# Myscheme.net
KiCad netlist of a schematic drawn in Altium Designer
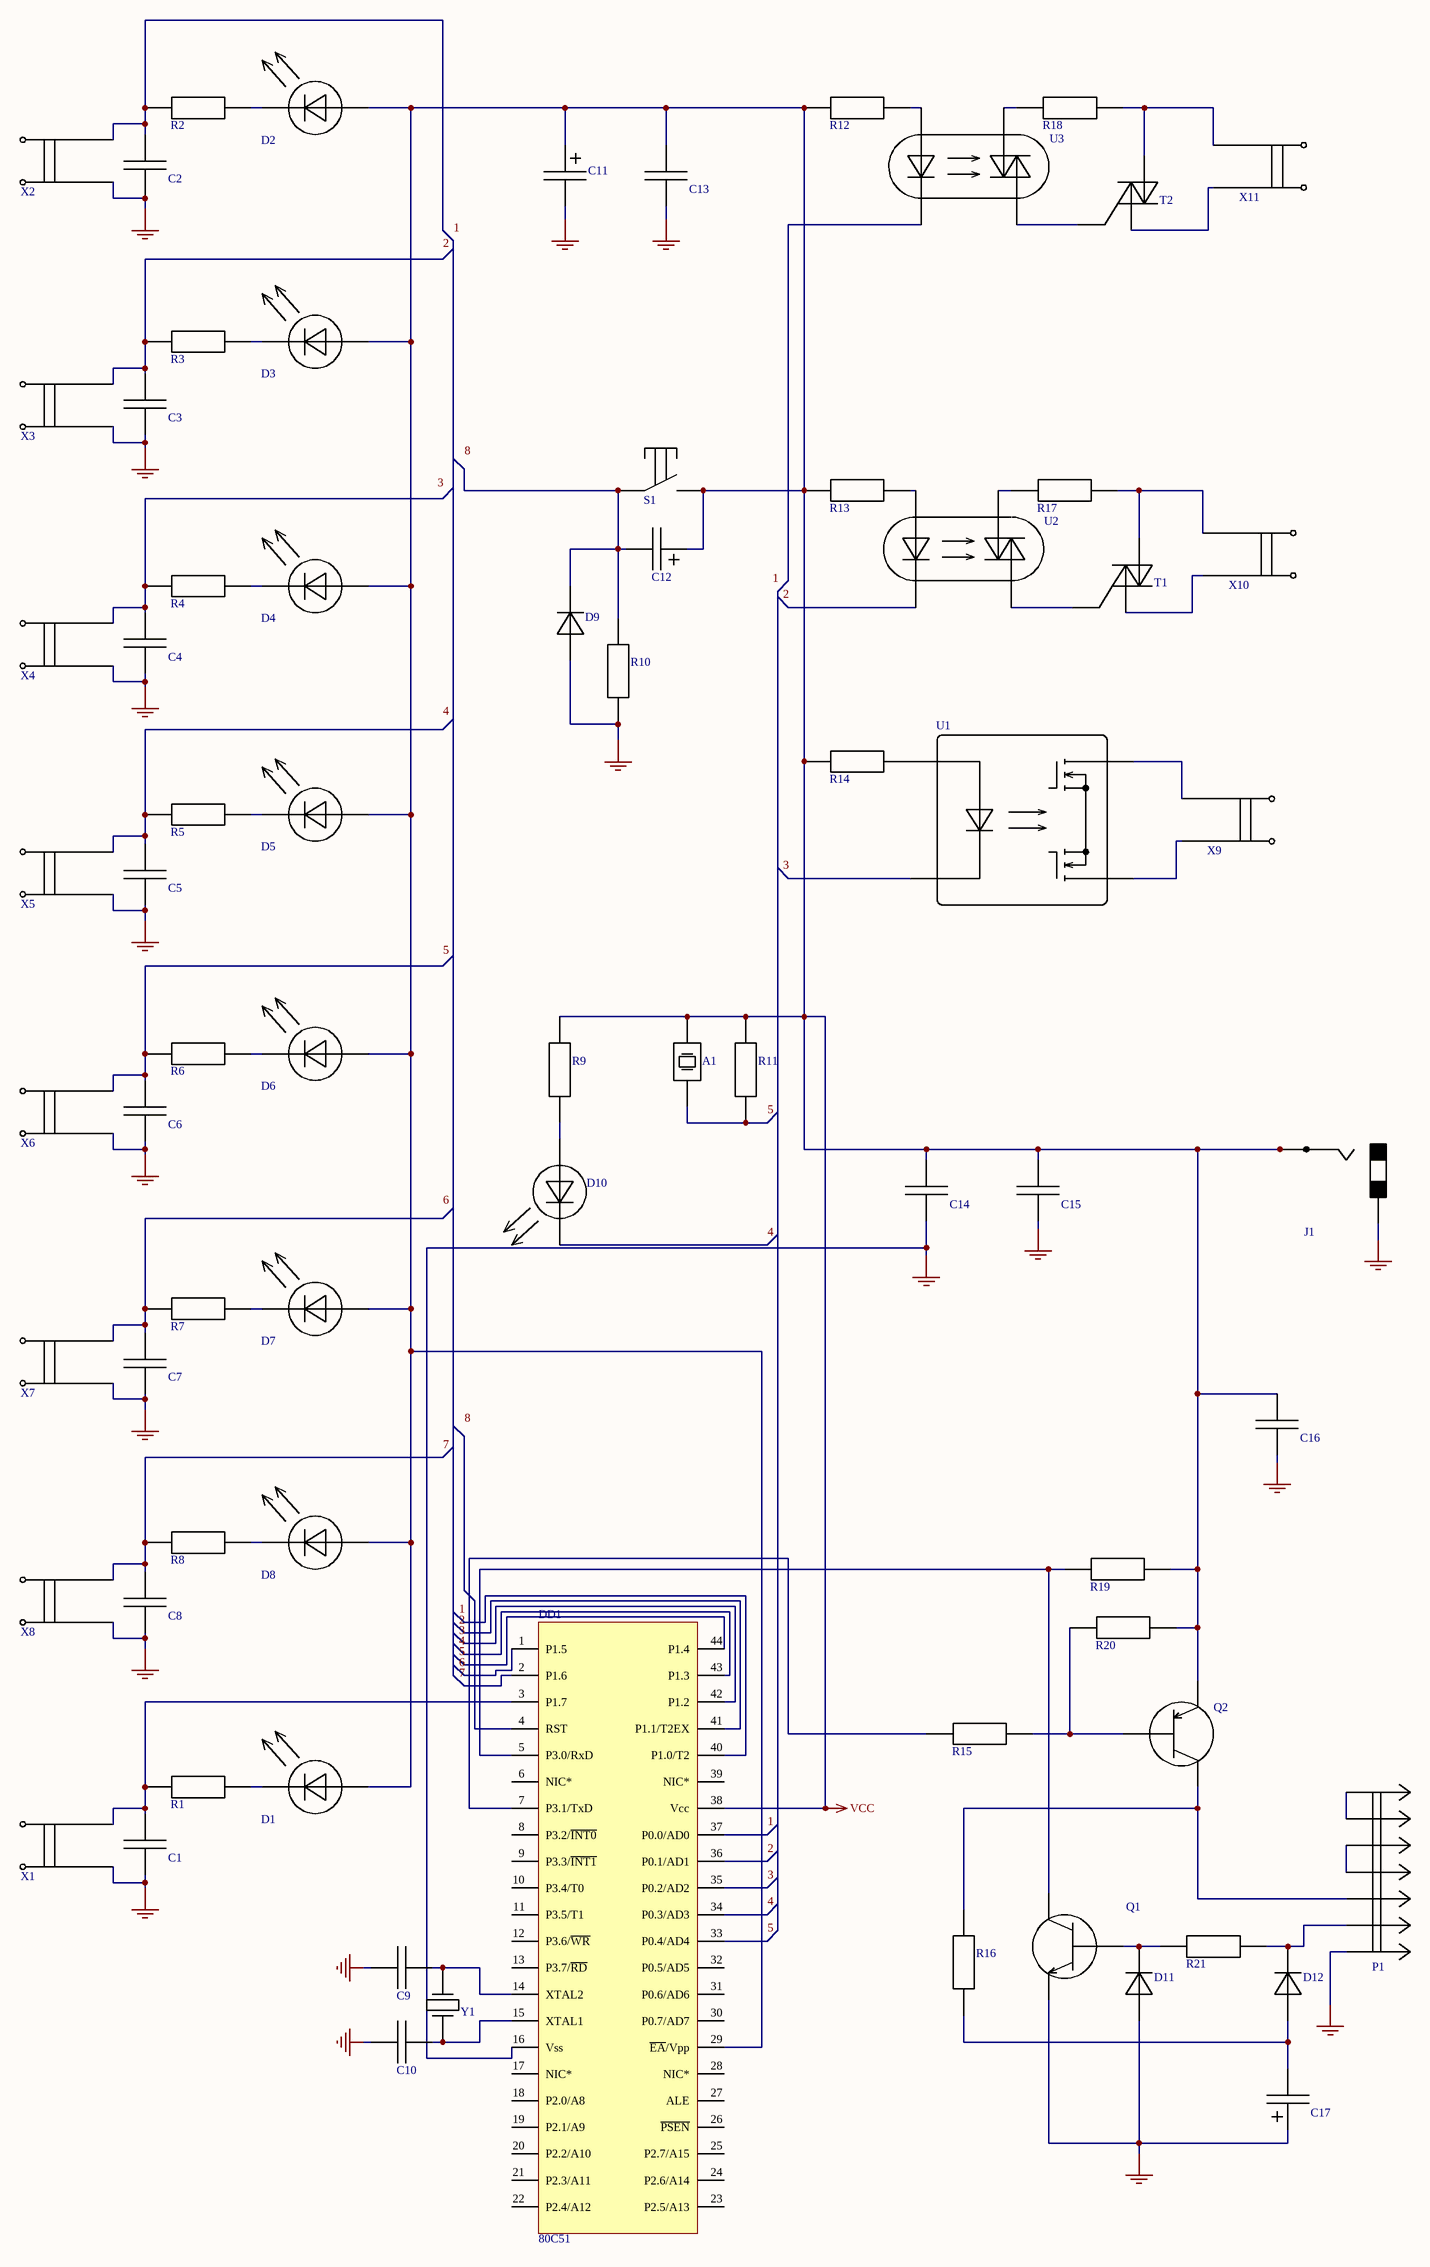
[diagram p0: Myscheme.SchDoc]

(export (version "E")
  (design (tool "Eeschema 10.0.6"))
  (components
    (comp (ref "A1")
      (value "acoustic")
      (footprint "PcbLib1:BUZZER_RM_5MM_PKM13EPYH4002-B0(Primary) - duplicate")
      (libsource (lib "Shestakov") (part "acoustic"))
    )
    (comp (ref "C1")
      (value "Cap")
      (footprint "RAD-0.3")
      (description "Capacitor")
      (libsource (lib "Shestakov") (part "Cap"))
    )
    (comp (ref "C2")
      (value "Cap")
      (footprint "RAD-0.3")
      (description "Capacitor")
      (libsource (lib "Shestakov") (part "Cap"))
    )
    (comp (ref "C3")
      (value "Cap")
      (footprint "RAD-0.3")
      (description "Capacitor")
      (libsource (lib "Shestakov") (part "Cap"))
    )
    (comp (ref "C4")
      (value "Cap")
      (footprint "RAD-0.3")
      (description "Capacitor")
      (libsource (lib "Shestakov") (part "Cap"))
    )
    (comp (ref "C5")
      (value "Cap")
      (footprint "RAD-0.3")
      (description "Capacitor")
      (libsource (lib "Shestakov") (part "Cap"))
    )
    (comp (ref "C6")
      (value "Cap")
      (footprint "RAD-0.3")
      (description "Capacitor")
      (libsource (lib "Shestakov") (part "Cap"))
    )
    (comp (ref "C7")
      (value "Cap")
      (footprint "RAD-0.3")
      (description "Capacitor")
      (libsource (lib "Shestakov") (part "Cap"))
    )
    (comp (ref "C8")
      (value "Cap")
      (footprint "RAD-0.3")
      (description "Capacitor")
      (libsource (lib "Shestakov") (part "Cap"))
    )
    (comp (ref "C9")
      (value "Cap")
      (footprint "RAD-0.3")
      (description "Capacitor")
      (libsource (lib "Shestakov") (part "Cap"))
    )
    (comp (ref "C10")
      (value "Cap")
      (footprint "RAD-0.3")
      (description "Capacitor")
      (libsource (lib "Shestakov") (part "Cap"))
    )
    (comp (ref "C11") (value "Cap+") (footprint "RB7.6-15") (libsource (lib "Shestakov") (part "Cap+")))
    (comp (ref "C12") (value "Cap+") (footprint "RB7.6-15") (libsource (lib "Shestakov") (part "Cap+")))
    (comp (ref "C13")
      (value "Cap")
      (footprint "RAD-0.3")
      (description "Capacitor")
      (libsource (lib "Shestakov") (part "Cap"))
    )
    (comp (ref "C14")
      (value "Cap")
      (footprint "RAD-0.3")
      (description "Capacitor")
      (libsource (lib "Shestakov") (part "Cap"))
    )
    (comp (ref "C15")
      (value "Cap")
      (footprint "RAD-0.3")
      (description "Capacitor")
      (libsource (lib "Shestakov") (part "Cap"))
    )
    (comp (ref "C16")
      (value "Cap")
      (footprint "RAD-0.3")
      (description "Capacitor")
      (libsource (lib "Shestakov") (part "Cap"))
    )
    (comp (ref "C17") (value "Cap+") (footprint "RB7.6-15") (libsource (lib "Shestakov") (part "Cap+")))
    (comp (ref "D1") (value "LED") (footprint "LED-1") (libsource (lib "Integrated_Library2") (part "LED")))
    (comp (ref "D2") (value "LED") (footprint "LED-1") (libsource (lib "Integrated_Library2") (part "LED")))
    (comp (ref "D3") (value "LED") (footprint "LED-1") (libsource (lib "Integrated_Library2") (part "LED")))
    (comp (ref "D4") (value "LED") (footprint "LED-1") (libsource (lib "Integrated_Library2") (part "LED")))
    (comp (ref "D5") (value "LED") (footprint "LED-1") (libsource (lib "Integrated_Library2") (part "LED")))
    (comp (ref "D6") (value "LED") (footprint "LED-1") (libsource (lib "Integrated_Library2") (part "LED")))
    (comp (ref "D7") (value "LED") (footprint "LED-1") (libsource (lib "Integrated_Library2") (part "LED")))
    (comp (ref "D8") (value "LED") (footprint "LED-1") (libsource (lib "Integrated_Library2") (part "LED")))
    (comp (ref "D9")
      (value "~")
      (footprint "PcbLib1:DIOAD730W55L340D162P_1N4148(Primary)")
      (description "1N4148")
      (libsource (lib "Shestakov") (part "1N4148"))
    )
    (comp (ref "D10") (value "LED") (footprint "LED-1") (libsource (lib "Integrated_Library2") (part "LED")))
    (comp (ref "D11")
      (value "~")
      (footprint "PcbLib1:DIOAD730W55L340D162P_1N4148(Primary)")
      (description "1N4148")
      (libsource (lib "Shestakov") (part "1N4148"))
    )
    (comp (ref "D12")
      (value "~")
      (footprint "PcbLib1:DIOAD730W55L340D162P_1N4148(Primary)")
      (description "1N4148")
      (libsource (lib "Shestakov") (part "1N4148"))
    )
    (comp (ref "DD1")
      (value "80C51")
      (footprint "QFP80P1260X1260X210-44N")
      (libsource (lib "Shestakov") (part "80C51"))
    )
    (comp (ref "J1")
      (value "phonejack")
      (footprint "PcbLib1:JACK/6-V2")
      (libsource (lib "Shestakov") (part "phonejack"))
    )
    (comp (ref "P1") (value "plug") (footprint "PIN1") (libsource (lib "Shestakov") (part "plug")))
    (comp (ref "Q1")
      (value "~")
      (footprint "PcbLib1:TO-92A")
      (description "КТ315Б")
      (libsource (lib "Shestakov") (part "КТ315Б"))
    )
    (comp (ref "Q2")
      (value "~")
      (footprint "PcbLib1:TO92127P520H534-3")
      (description "КТ361Б")
      (libsource (lib "Shestakov") (part "КТ361Б"))
    )
    (comp (ref "R1")
      (value "Res")
      (footprint "PCBComponent_1")
      (libsource (lib "Integrated_Library2") (part "Res"))
    )
    (comp (ref "R2")
      (value "Res")
      (footprint "PCBComponent_1")
      (libsource (lib "Integrated_Library2") (part "Res"))
    )
    (comp (ref "R3")
      (value "Res")
      (footprint "PCBComponent_1")
      (libsource (lib "Integrated_Library2") (part "Res"))
    )
    (comp (ref "R4")
      (value "Res")
      (footprint "PCBComponent_1")
      (libsource (lib "Integrated_Library2") (part "Res"))
    )
    (comp (ref "R5")
      (value "Res")
      (footprint "PCBComponent_1")
      (libsource (lib "Integrated_Library2") (part "Res"))
    )
    (comp (ref "R6")
      (value "Res")
      (footprint "PCBComponent_1")
      (libsource (lib "Integrated_Library2") (part "Res"))
    )
    (comp (ref "R7")
      (value "Res")
      (footprint "PCBComponent_1")
      (libsource (lib "Integrated_Library2") (part "Res"))
    )
    (comp (ref "R8")
      (value "Res")
      (footprint "PCBComponent_1")
      (libsource (lib "Integrated_Library2") (part "Res"))
    )
    (comp (ref "R9")
      (value "Res")
      (footprint "PCBComponent_1")
      (libsource (lib "Integrated_Library2") (part "Res"))
    )
    (comp (ref "R10")
      (value "Res")
      (footprint "PCBComponent_1")
      (libsource (lib "Integrated_Library2") (part "Res"))
    )
    (comp (ref "R11")
      (value "Res")
      (footprint "PCBComponent_1")
      (libsource (lib "Integrated_Library2") (part "Res"))
    )
    (comp (ref "R12")
      (value "Res")
      (footprint "PCBComponent_1")
      (libsource (lib "Integrated_Library2") (part "Res"))
    )
    (comp (ref "R13")
      (value "Res")
      (footprint "PCBComponent_1")
      (libsource (lib "Integrated_Library2") (part "Res"))
    )
    (comp (ref "R14")
      (value "Res")
      (footprint "PCBComponent_1")
      (libsource (lib "Integrated_Library2") (part "Res"))
    )
    (comp (ref "R15")
      (value "Res")
      (footprint "PCBComponent_1")
      (libsource (lib "Integrated_Library2") (part "Res"))
    )
    (comp (ref "R16")
      (value "Res")
      (footprint "PCBComponent_1")
      (libsource (lib "Integrated_Library2") (part "Res"))
    )
    (comp (ref "R17")
      (value "Res")
      (footprint "PCBComponent_1")
      (libsource (lib "Integrated_Library2") (part "Res"))
    )
    (comp (ref "R18")
      (value "Res")
      (footprint "PCBComponent_1")
      (libsource (lib "Integrated_Library2") (part "Res"))
    )
    (comp (ref "R19")
      (value "Res")
      (footprint "PCBComponent_1")
      (libsource (lib "Integrated_Library2") (part "Res"))
    )
    (comp (ref "R20")
      (value "Res")
      (footprint "PCBComponent_1")
      (libsource (lib "Integrated_Library2") (part "Res"))
    )
    (comp (ref "R21")
      (value "Res")
      (footprint "PCBComponent_1")
      (libsource (lib "Integrated_Library2") (part "Res"))
    )
    (comp (ref "S1") (value "SW-SPST") (footprint "SPST-2") (libsource (lib "Shestakov") (part "SW-SPST")))
    (comp (ref "T1")
      (value "~")
      (footprint "PcbLib1:TO-220-ALT")
      (description "BT138-600")
      (libsource (lib "Shestakov") (part "BT138-600"))
    )
    (comp (ref "T2")
      (value "~")
      (footprint "PcbLib1:TO-220-ALT")
      (description "BT138-600")
      (libsource (lib "Shestakov") (part "BT138-600"))
    )
    (comp (ref "U1")
      (value "~")
      (footprint "PcbLib1:SOIC254P610X218-4N")
      (description "CPC1035N")
      (libsource (lib "Shestakov") (part "CPC1035N"))
    )
    (comp (ref "U2")
      (value "~")
      (footprint "PcbLib1:SOIC254P1016X460-6N")
      (description "MOC3020M")
      (libsource (lib "Shestakov") (part "MOC3020M"))
    )
    (comp (ref "U3")
      (value "~")
      (footprint "PcbLib1:SOIC254P1016X460-6N")
      (description "MOC3020M")
      (libsource (lib "Shestakov") (part "MOC3020M"))
    )
    (comp (ref "X1")
      (value "Entrance")
      (footprint "PcbLib1:P-2059-301/998-403_2059-301/998-403(Primary)")
      (libsource (lib "Shestakov") (part "Entrance"))
    )
    (comp (ref "X2")
      (value "Entrance")
      (footprint "PcbLib1:P-2059-301/998-403_2059-301/998-403(Primary)")
      (libsource (lib "Shestakov") (part "Entrance"))
    )
    (comp (ref "X3")
      (value "Entrance")
      (footprint "PcbLib1:P-2059-301/998-403_2059-301/998-403(Primary)")
      (libsource (lib "Shestakov") (part "Entrance"))
    )
    (comp (ref "X4")
      (value "Entrance")
      (footprint "PcbLib1:P-2059-301/998-403_2059-301/998-403(Primary)")
      (libsource (lib "Shestakov") (part "Entrance"))
    )
    (comp (ref "X5")
      (value "Entrance")
      (footprint "PcbLib1:P-2059-301/998-403_2059-301/998-403(Primary)")
      (libsource (lib "Shestakov") (part "Entrance"))
    )
    (comp (ref "X6")
      (value "Entrance")
      (footprint "PcbLib1:P-2059-301/998-403_2059-301/998-403(Primary)")
      (libsource (lib "Shestakov") (part "Entrance"))
    )
    (comp (ref "X7")
      (value "Entrance")
      (footprint "PcbLib1:P-2059-301/998-403_2059-301/998-403(Primary)")
      (libsource (lib "Shestakov") (part "Entrance"))
    )
    (comp (ref "X8")
      (value "Entrance")
      (footprint "PcbLib1:P-2059-301/998-403_2059-301/998-403(Primary)")
      (libsource (lib "Shestakov") (part "Entrance"))
    )
    (comp (ref "X9")
      (value "Entrance")
      (footprint "PcbLib1:P-2059-301/998-403_2059-301/998-403(Primary)")
      (libsource (lib "Shestakov") (part "Entrance"))
    )
    (comp (ref "X10")
      (value "Entrance")
      (footprint "PcbLib1:P-2059-301/998-403_2059-301/998-403(Primary)")
      (libsource (lib "Shestakov") (part "Entrance"))
    )
    (comp (ref "X11")
      (value "Entrance")
      (footprint "PcbLib1:P-2059-301/998-403_2059-301/998-403(Primary)")
      (libsource (lib "Shestakov") (part "Entrance"))
    )
    (comp (ref "Y1") (value "XTAL") (footprint "R38") (libsource (lib "Shestakov") (part "XTAL")))
  )
  (nets
    (net (code "9") (name "GND") (class "Default")
      (node (ref "C1") (pin "2") (pinfunction "2_2") (pintype "passive"))
      (node (ref "C10") (pin "2") (pinfunction "2_2") (pintype "passive"))
      (node (ref "C11") (pin "2") (pinfunction "2_2") (pintype "passive"))
      (node (ref "C13") (pin "2") (pinfunction "2_2") (pintype "passive"))
      (node (ref "C14") (pin "2") (pinfunction "2_2") (pintype "passive"))
      (node (ref "C15") (pin "2") (pinfunction "2_2") (pintype "passive"))
      (node (ref "C16") (pin "2") (pinfunction "2_2") (pintype "passive"))
      (node (ref "C17") (pin "1") (pinfunction "1_1") (pintype "passive"))
      (node (ref "C2") (pin "2") (pinfunction "2_2") (pintype "passive"))
      (node (ref "C3") (pin "2") (pinfunction "2_2") (pintype "passive"))
      (node (ref "C4") (pin "2") (pinfunction "2_2") (pintype "passive"))
      (node (ref "C5") (pin "2") (pinfunction "2_2") (pintype "passive"))
      (node (ref "C6") (pin "2") (pinfunction "2_2") (pintype "passive"))
      (node (ref "C7") (pin "2") (pinfunction "2_2") (pintype "passive"))
      (node (ref "C8") (pin "2") (pinfunction "2_2") (pintype "passive"))
      (node (ref "C9") (pin "2") (pinfunction "2_2") (pintype "passive"))
      (node (ref "D11") (pin "C") (pinfunction "C_C") (pintype "passive"))
      (node (ref "D9") (pin "C") (pinfunction "C_C") (pintype "passive"))
      (node (ref "DD1") (pin "16") (pinfunction "Vss_16") (pintype "power_in"))
      (node (ref "J1") (pin "5") (pinfunction "5_5") (pintype "passive"))
      (node (ref "P1") (pin "5") (pinfunction "5_5") (pintype "passive"))
      (node (ref "Q1") (pin "1") (pinfunction "1_1") (pintype "passive"))
      (node (ref "R10") (pin "2") (pinfunction "2_2") (pintype "passive"))
      (node (ref "X1") (pin "L1.2") (pinfunction "2_L1.2") (pintype "passive"))
      (node (ref "X2") (pin "L1.2") (pinfunction "2_L1.2") (pintype "passive"))
      (node (ref "X3") (pin "L1.2") (pinfunction "2_L1.2") (pintype "passive"))
      (node (ref "X4") (pin "L1.2") (pinfunction "2_L1.2") (pintype "passive"))
      (node (ref "X5") (pin "L1.2") (pinfunction "2_L1.2") (pintype "passive"))
      (node (ref "X6") (pin "L1.2") (pinfunction "2_L1.2") (pintype "passive"))
      (node (ref "X7") (pin "L1.2") (pinfunction "2_L1.2") (pintype "passive"))
      (node (ref "X8") (pin "L1.2") (pinfunction "2_L1.2") (pintype "passive"))
    )
    (net (code "10") (name "Net-(A1-PadPOS)") (class "Default")
      (node (ref "A1") (pin "POS") (pinfunction "POS_POS") (pintype "passive"))
      (node (ref "R11") (pin "2") (pinfunction "2_2") (pintype "passive"))
    )
    (net (code "11") (name "Net-(C12-Pad2)") (class "Default")
      (node (ref "C12") (pin "2") (pinfunction "2_2") (pintype "passive"))
      (node (ref "D9") (pin "A") (pinfunction "A_A") (pintype "passive"))
      (node (ref "R10") (pin "1") (pinfunction "1_1") (pintype "passive"))
      (node (ref "S1") (pin "1") (pinfunction "1_1") (pintype "passive"))
    )
    (net (code "12") (name "Net-(C17-Pad2)") (class "Default")
      (node (ref "C17") (pin "2") (pinfunction "2_2") (pintype "passive"))
      (node (ref "D12") (pin "C") (pinfunction "C_C") (pintype "passive"))
      (node (ref "R16") (pin "1") (pinfunction "1_1") (pintype "passive"))
    )
    (net (code "13") (name "Net-(D1-Pad1)") (class "Default")
      (node (ref "D1") (pin "1") (pinfunction "1_1") (pintype "passive"))
      (node (ref "R1") (pin "1") (pinfunction "1_1") (pintype "passive"))
    )
    (net (code "14") (name "Net-(D2-Pad1)") (class "Default")
      (node (ref "D2") (pin "1") (pinfunction "1_1") (pintype "passive"))
      (node (ref "R2") (pin "1") (pinfunction "1_1") (pintype "passive"))
    )
    (net (code "15") (name "Net-(D3-Pad1)") (class "Default")
      (node (ref "D3") (pin "1") (pinfunction "1_1") (pintype "passive"))
      (node (ref "R3") (pin "1") (pinfunction "1_1") (pintype "passive"))
    )
    (net (code "16") (name "Net-(D4-Pad1)") (class "Default")
      (node (ref "D4") (pin "1") (pinfunction "1_1") (pintype "passive"))
      (node (ref "R4") (pin "1") (pinfunction "1_1") (pintype "passive"))
    )
    (net (code "17") (name "Net-(D5-Pad1)") (class "Default")
      (node (ref "D5") (pin "1") (pinfunction "1_1") (pintype "passive"))
      (node (ref "R5") (pin "1") (pinfunction "1_1") (pintype "passive"))
    )
    (net (code "18") (name "Net-(D6-Pad1)") (class "Default")
      (node (ref "D6") (pin "1") (pinfunction "1_1") (pintype "passive"))
      (node (ref "R6") (pin "1") (pinfunction "1_1") (pintype "passive"))
    )
    (net (code "19") (name "Net-(D7-Pad1)") (class "Default")
      (node (ref "D7") (pin "1") (pinfunction "1_1") (pintype "passive"))
      (node (ref "R7") (pin "1") (pinfunction "1_1") (pintype "passive"))
    )
    (net (code "20") (name "Net-(D8-Pad1)") (class "Default")
      (node (ref "D8") (pin "1") (pinfunction "1_1") (pintype "passive"))
      (node (ref "R8") (pin "1") (pinfunction "1_1") (pintype "passive"))
    )
    (net (code "21") (name "Net-(D10-Pad2)") (class "Default")
      (node (ref "D10") (pin "2") (pinfunction "2_2") (pintype "passive"))
      (node (ref "R9") (pin "2") (pinfunction "2_2") (pintype "passive"))
    )
    (net (code "22") (name "Net-(D11-PadA)") (class "Default")
      (node (ref "D11") (pin "A") (pinfunction "A_A") (pintype "passive"))
      (node (ref "Q1") (pin "2") (pinfunction "2_2") (pintype "passive"))
      (node (ref "R21") (pin "1") (pinfunction "1_1") (pintype "passive"))
    )
    (net (code "23") (name "Net-(D12-PadA)") (class "Default")
      (node (ref "D12") (pin "A") (pinfunction "A_A") (pintype "passive"))
      (node (ref "P1") (pin "2") (pinfunction "2_2") (pintype "passive"))
      (node (ref "R21") (pin "2") (pinfunction "2_2") (pintype "passive"))
    )
    (net (code "24") (name "Net-(DD1-P1.7)") (class "Default")
      (node (ref "C1") (pin "1") (pinfunction "1_1") (pintype "passive"))
      (node (ref "DD1") (pin "3") (pinfunction "P1.7_3") (pintype "passive"))
      (node (ref "R1") (pin "2") (pinfunction "2_2") (pintype "passive"))
      (node (ref "X1") (pin "L1.1") (pinfunction "1_L1.1") (pintype "passive"))
    )
    (net (code "25") (name "Net-(DD1-P3.0{slash}RxD)") (class "Default")
      (node (ref "DD1") (pin "5") (pinfunction "P3.0/RxD_5") (pintype "passive"))
      (node (ref "Q1") (pin "3") (pinfunction "3_3") (pintype "passive"))
      (node (ref "R19") (pin "1") (pinfunction "1_1") (pintype "passive"))
    )
    (net (code "26") (name "Net-(DD1-P3.1{slash}TxD)") (class "Default")
      (node (ref "DD1") (pin "7") (pinfunction "P3.1/TxD_7") (pintype "passive"))
      (node (ref "R15") (pin "1") (pinfunction "1_1") (pintype "passive"))
    )
    (net (code "27") (name "Net-(DD1-XTAL1)") (class "Default")
      (node (ref "C10") (pin "1") (pinfunction "1_1") (pintype "passive"))
      (node (ref "DD1") (pin "15") (pinfunction "XTAL1_15") (pintype "passive"))
      (node (ref "Y1") (pin "1") (pinfunction "1_1") (pintype "passive"))
    )
    (net (code "28") (name "Net-(DD1-XTAL2)") (class "Default")
      (node (ref "C9") (pin "1") (pinfunction "1_1") (pintype "passive"))
      (node (ref "DD1") (pin "14") (pinfunction "XTAL2_14") (pintype "passive"))
      (node (ref "Y1") (pin "2") (pinfunction "2_2") (pintype "passive"))
    )
    (net (code "29") (name "Net-(P1-Pad3)") (class "Default")
      (node (ref "P1") (pin "3") (pinfunction "3_3") (pintype "passive"))
      (node (ref "Q2") (pin "3") (pinfunction "3_3") (pintype "passive"))
      (node (ref "R16") (pin "2") (pinfunction "2_2") (pintype "passive"))
    )
    (net (code "30") (name "Net-(P1-Pad4)") (class "Default")
      (node (ref "P1") (pin "4") (pinfunction "4_4") (pintype "passive"))
      (node (ref "P1") (pin "6") (pinfunction "6_6") (pintype "passive"))
    )
    (net (code "31") (name "Net-(P1-Pad7)") (class "Default")
      (node (ref "P1") (pin "7") (pinfunction "7_7") (pintype "passive"))
      (node (ref "P1") (pin "8") (pinfunction "8_8") (pintype "passive"))
    )
    (net (code "32") (name "Net-(Q2-Pad2)") (class "Default")
      (node (ref "Q2") (pin "2") (pinfunction "2_2") (pintype "passive"))
      (node (ref "R15") (pin "2") (pinfunction "2_2") (pintype "passive"))
      (node (ref "R20") (pin "1") (pinfunction "1_1") (pintype "passive"))
    )
    (net (code "33") (name "Net-(R12-Pad1)") (class "Default")
      (node (ref "R12") (pin "1") (pinfunction "1_1") (pintype "passive"))
      (node (ref "U3") (pin "1") (pinfunction "1_1") (pintype "passive"))
    )
    (net (code "34") (name "Net-(R13-Pad1)") (class "Default")
      (node (ref "R13") (pin "1") (pinfunction "1_1") (pintype "passive"))
      (node (ref "U2") (pin "1") (pinfunction "1_1") (pintype "passive"))
    )
    (net (code "35") (name "Net-(R14-Pad1)") (class "Default")
      (node (ref "R14") (pin "1") (pinfunction "1_1") (pintype "passive"))
      (node (ref "U1") (pin "1") (pinfunction "1_1") (pintype "passive"))
    )
    (net (code "36") (name "Net-(R17-Pad2)") (class "Default")
      (node (ref "R17") (pin "2") (pinfunction "2_2") (pintype "passive"))
      (node (ref "U2") (pin "6") (pinfunction "6_6") (pintype "passive"))
    )
    (net (code "37") (name "Net-(R18-Pad2)") (class "Default")
      (node (ref "R18") (pin "2") (pinfunction "2_2") (pintype "passive"))
      (node (ref "U3") (pin "6") (pinfunction "6_6") (pintype "passive"))
    )
    (net (code "38") (name "Net-(T1-PadOUT)") (class "Default")
      (node (ref "T1") (pin "OUT") (pinfunction "OUT_OUT") (pintype "passive"))
      (node (ref "U2") (pin "4") (pinfunction "4_4") (pintype "passive"))
    )
    (net (code "39") (name "Net-(T2-PadOUT)") (class "Default")
      (node (ref "T2") (pin "OUT") (pinfunction "OUT_OUT") (pintype "passive"))
      (node (ref "U3") (pin "4") (pinfunction "4_4") (pintype "passive"))
    )
    (net (code "40") (name "Net-(X2-1)") (class "Default")
      (node (ref "C2") (pin "1") (pinfunction "1_1") (pintype "passive"))
      (node (ref "R2") (pin "2") (pinfunction "2_2") (pintype "passive"))
      (node (ref "X2") (pin "L1.1") (pinfunction "1_L1.1") (pintype "passive"))
    )
    (net (code "41") (name "Net-(X3-1)") (class "Default")
      (node (ref "C3") (pin "1") (pinfunction "1_1") (pintype "passive"))
      (node (ref "R3") (pin "2") (pinfunction "2_2") (pintype "passive"))
      (node (ref "X3") (pin "L1.1") (pinfunction "1_L1.1") (pintype "passive"))
    )
    (net (code "42") (name "Net-(X4-1)") (class "Default")
      (node (ref "C4") (pin "1") (pinfunction "1_1") (pintype "passive"))
      (node (ref "R4") (pin "2") (pinfunction "2_2") (pintype "passive"))
      (node (ref "X4") (pin "L1.1") (pinfunction "1_L1.1") (pintype "passive"))
    )
    (net (code "43") (name "Net-(X5-1)") (class "Default")
      (node (ref "C5") (pin "1") (pinfunction "1_1") (pintype "passive"))
      (node (ref "R5") (pin "2") (pinfunction "2_2") (pintype "passive"))
      (node (ref "X5") (pin "L1.1") (pinfunction "1_L1.1") (pintype "passive"))
    )
    (net (code "44") (name "Net-(X6-1)") (class "Default")
      (node (ref "C6") (pin "1") (pinfunction "1_1") (pintype "passive"))
      (node (ref "R6") (pin "2") (pinfunction "2_2") (pintype "passive"))
      (node (ref "X6") (pin "L1.1") (pinfunction "1_L1.1") (pintype "passive"))
    )
    (net (code "45") (name "Net-(X7-1)") (class "Default")
      (node (ref "C7") (pin "1") (pinfunction "1_1") (pintype "passive"))
      (node (ref "R7") (pin "2") (pinfunction "2_2") (pintype "passive"))
      (node (ref "X7") (pin "L1.1") (pinfunction "1_L1.1") (pintype "passive"))
    )
    (net (code "46") (name "Net-(X8-1)") (class "Default")
      (node (ref "C8") (pin "1") (pinfunction "1_1") (pintype "passive"))
      (node (ref "R8") (pin "2") (pinfunction "2_2") (pintype "passive"))
      (node (ref "X8") (pin "L1.1") (pinfunction "1_L1.1") (pintype "passive"))
    )
    (net (code "47") (name "Net-(X9-1)") (class "Default")
      (node (ref "U1") (pin "4") (pinfunction "4_4") (pintype "passive"))
      (node (ref "X9") (pin "L1.1") (pinfunction "1_L1.1") (pintype "passive"))
    )
    (net (code "48") (name "Net-(X9-2)") (class "Default")
      (node (ref "U1") (pin "3") (pinfunction "3_3") (pintype "passive"))
      (node (ref "X9") (pin "L1.2") (pinfunction "2_L1.2") (pintype "passive"))
    )
    (net (code "49") (name "Net-(X10-1)") (class "Default")
      (node (ref "T1") (pin "IN") (pinfunction "IN_IN") (pintype "passive"))
      (node (ref "X10") (pin "L1.1") (pinfunction "1_L1.1") (pintype "passive"))
    )
    (net (code "50") (name "Net-(X10-2)") (class "Default")
      (node (ref "R17") (pin "1") (pinfunction "1_1") (pintype "passive"))
      (node (ref "T1") (pin "GND") (pinfunction "GND_GND") (pintype "passive"))
      (node (ref "X10") (pin "L1.2") (pinfunction "2_L1.2") (pintype "passive"))
    )
    (net (code "51") (name "Net-(X11-1)") (class "Default")
      (node (ref "T2") (pin "IN") (pinfunction "IN_IN") (pintype "passive"))
      (node (ref "X11") (pin "L1.1") (pinfunction "1_L1.1") (pintype "passive"))
    )
    (net (code "52") (name "Net-(X11-2)") (class "Default")
      (node (ref "R18") (pin "1") (pinfunction "1_1") (pintype "passive"))
      (node (ref "T2") (pin "GND") (pinfunction "GND_GND") (pintype "passive"))
      (node (ref "X11") (pin "L1.2") (pinfunction "2_L1.2") (pintype "passive"))
    )
    (net (code "53") (name "VCC") (class "Default")
      (node (ref "A1") (pin "NEG") (pinfunction "NEG_NEG") (pintype "passive"))
      (node (ref "C11") (pin "1") (pinfunction "1_1") (pintype "passive"))
      (node (ref "C12") (pin "1") (pinfunction "1_1") (pintype "passive"))
      (node (ref "C13") (pin "1") (pinfunction "1_1") (pintype "passive"))
      (node (ref "C14") (pin "1") (pinfunction "1_1") (pintype "passive"))
      (node (ref "C15") (pin "1") (pinfunction "1_1") (pintype "passive"))
      (node (ref "C16") (pin "1") (pinfunction "1_1") (pintype "passive"))
      (node (ref "D1") (pin "2") (pinfunction "2_2") (pintype "passive"))
      (node (ref "D2") (pin "2") (pinfunction "2_2") (pintype "passive"))
      (node (ref "D3") (pin "2") (pinfunction "2_2") (pintype "passive"))
      (node (ref "D4") (pin "2") (pinfunction "2_2") (pintype "passive"))
      (node (ref "D5") (pin "2") (pinfunction "2_2") (pintype "passive"))
      (node (ref "D6") (pin "2") (pinfunction "2_2") (pintype "passive"))
      (node (ref "D7") (pin "2") (pinfunction "2_2") (pintype "passive"))
      (node (ref "D8") (pin "2") (pinfunction "2_2") (pintype "passive"))
      (node (ref "DD1") (pin "29") (pinfunction "~{EA}/Vpp_29") (pintype "passive"))
      (node (ref "DD1") (pin "38") (pinfunction "Vcc_38") (pintype "power_in"))
      (node (ref "J1") (pin "1") (pinfunction "1_1") (pintype "passive"))
      (node (ref "Q2") (pin "1") (pinfunction "1_1") (pintype "passive"))
      (node (ref "R11") (pin "1") (pinfunction "1_1") (pintype "passive"))
      (node (ref "R12") (pin "2") (pinfunction "2_2") (pintype "passive"))
      (node (ref "R13") (pin "2") (pinfunction "2_2") (pintype "passive"))
      (node (ref "R14") (pin "2") (pinfunction "2_2") (pintype "passive"))
      (node (ref "R19") (pin "2") (pinfunction "2_2") (pintype "passive"))
      (node (ref "R20") (pin "2") (pinfunction "2_2") (pintype "passive"))
      (node (ref "R9") (pin "1") (pinfunction "1_1") (pintype "passive"))
      (node (ref "S1") (pin "2") (pinfunction "2_2") (pintype "passive"))
    )
    (net (code "54") (name "unconnected-(D10-Pad1)") (class "Default")
      (node (ref "D10") (pin "1") (pinfunction "1_1") (pintype "passive"))
    )
    (net (code "55") (name "unconnected-(DD1-ALE-Pad27)") (class "Default")
      (node (ref "DD1") (pin "27") (pinfunction "ALE_27") (pintype "passive"))
    )
    (net (code "56") (name "unconnected-(DD1-NIC*-Pad6)") (class "Default")
      (node (ref "DD1") (pin "6") (pinfunction "NIC*_6") (pintype "passive"))
    )
    (net (code "57") (name "unconnected-(DD1-NIC*-Pad17)") (class "Default")
      (node (ref "DD1") (pin "17") (pinfunction "NIC*_17") (pintype "passive"))
    )
    (net (code "58") (name "unconnected-(DD1-NIC*-Pad28)") (class "Default")
      (node (ref "DD1") (pin "28") (pinfunction "NIC*_28") (pintype "passive"))
    )
    (net (code "59") (name "unconnected-(DD1-NIC*-Pad39)") (class "Default")
      (node (ref "DD1") (pin "39") (pinfunction "NIC*_39") (pintype "passive"))
    )
    (net (code "60") (name "unconnected-(DD1-P0.0{slash}AD0-Pad37)") (class "Default")
      (node (ref "DD1") (pin "37") (pinfunction "P0.0/AD0_37") (pintype "passive"))
    )
    (net (code "61") (name "unconnected-(DD1-P0.1{slash}AD1-Pad36)") (class "Default")
      (node (ref "DD1") (pin "36") (pinfunction "P0.1/AD1_36") (pintype "passive"))
    )
    (net (code "62") (name "unconnected-(DD1-P0.2{slash}AD2-Pad35)") (class "Default")
      (node (ref "DD1") (pin "35") (pinfunction "P0.2/AD2_35") (pintype "passive"))
    )
    (net (code "63") (name "unconnected-(DD1-P0.3{slash}AD3-Pad34)") (class "Default")
      (node (ref "DD1") (pin "34") (pinfunction "P0.3/AD3_34") (pintype "passive"))
    )
    (net (code "64") (name "unconnected-(DD1-P0.4{slash}AD4-Pad33)") (class "Default")
      (node (ref "DD1") (pin "33") (pinfunction "P0.4/AD4_33") (pintype "passive"))
    )
    (net (code "65") (name "unconnected-(DD1-P0.5{slash}AD5-Pad32)") (class "Default")
      (node (ref "DD1") (pin "32") (pinfunction "P0.5/AD5_32") (pintype "passive"))
    )
    (net (code "66") (name "unconnected-(DD1-P0.6{slash}AD6-Pad31)") (class "Default")
      (node (ref "DD1") (pin "31") (pinfunction "P0.6/AD6_31") (pintype "passive"))
    )
    (net (code "67") (name "unconnected-(DD1-P0.7{slash}AD7-Pad30)") (class "Default")
      (node (ref "DD1") (pin "30") (pinfunction "P0.7/AD7_30") (pintype "passive"))
    )
    (net (code "68") (name "unconnected-(DD1-P1.0{slash}T2-Pad40)") (class "Default")
      (node (ref "DD1") (pin "40") (pinfunction "P1.0/T2_40") (pintype "passive"))
    )
    (net (code "69") (name "unconnected-(DD1-P1.1{slash}T2EX-Pad41)") (class "Default")
      (node (ref "DD1") (pin "41") (pinfunction "P1.1/T2EX_41") (pintype "passive"))
    )
    (net (code "70") (name "unconnected-(DD1-P1.2-Pad42)") (class "Default")
      (node (ref "DD1") (pin "42") (pinfunction "P1.2_42") (pintype "passive"))
    )
    (net (code "71") (name "unconnected-(DD1-P1.3-Pad43)") (class "Default")
      (node (ref "DD1") (pin "43") (pinfunction "P1.3_43") (pintype "passive"))
    )
    (net (code "72") (name "unconnected-(DD1-P1.4-Pad44)") (class "Default")
      (node (ref "DD1") (pin "44") (pinfunction "P1.4_44") (pintype "passive"))
    )
    (net (code "73") (name "unconnected-(DD1-P1.5-Pad1)") (class "Default")
      (node (ref "DD1") (pin "1") (pinfunction "P1.5_1") (pintype "passive"))
    )
    (net (code "74") (name "unconnected-(DD1-P1.6-Pad2)") (class "Default")
      (node (ref "DD1") (pin "2") (pinfunction "P1.6_2") (pintype "passive"))
    )
    (net (code "75") (name "unconnected-(DD1-P2.0{slash}A8-Pad18)") (class "Default")
      (node (ref "DD1") (pin "18") (pinfunction "P2.0/A8_18") (pintype "passive"))
    )
    (net (code "76") (name "unconnected-(DD1-P2.1{slash}A9-Pad19)") (class "Default")
      (node (ref "DD1") (pin "19") (pinfunction "P2.1/A9_19") (pintype "passive"))
    )
    (net (code "77") (name "unconnected-(DD1-P2.2{slash}A10-Pad20)") (class "Default")
      (node (ref "DD1") (pin "20") (pinfunction "P2.2/A10_20") (pintype "passive"))
    )
    (net (code "78") (name "unconnected-(DD1-P2.3{slash}A11-Pad21)") (class "Default")
      (node (ref "DD1") (pin "21") (pinfunction "P2.3/A11_21") (pintype "passive"))
    )
    (net (code "79") (name "unconnected-(DD1-P2.4{slash}A12-Pad22)") (class "Default")
      (node (ref "DD1") (pin "22") (pinfunction "P2.4/A12_22") (pintype "passive"))
    )
    (net (code "80") (name "unconnected-(DD1-P2.5{slash}A13-Pad23)") (class "Default")
      (node (ref "DD1") (pin "23") (pinfunction "P2.5/A13_23") (pintype "passive"))
    )
    (net (code "81") (name "unconnected-(DD1-P2.6{slash}A14-Pad24)") (class "Default")
      (node (ref "DD1") (pin "24") (pinfunction "P2.6/A14_24") (pintype "passive"))
    )
    (net (code "82") (name "unconnected-(DD1-P2.7{slash}A15-Pad25)") (class "Default")
      (node (ref "DD1") (pin "25") (pinfunction "P2.7/A15_25") (pintype "passive"))
    )
    (net (code "83") (name "unconnected-(DD1-P3.2{slash}~{INT0}-Pad8)") (class "Default")
      (node (ref "DD1") (pin "8") (pinfunction "P3.2/~{INT0}_8") (pintype "passive"))
    )
    (net (code "84") (name "unconnected-(DD1-P3.3{slash}~{INT1}-Pad9)") (class "Default")
      (node (ref "DD1") (pin "9") (pinfunction "P3.3/~{INT1}_9") (pintype "passive"))
    )
    (net (code "85") (name "unconnected-(DD1-P3.4{slash}T0-Pad10)") (class "Default")
      (node (ref "DD1") (pin "10") (pinfunction "P3.4/T0_10") (pintype "passive"))
    )
    (net (code "86") (name "unconnected-(DD1-P3.5{slash}T1-Pad11)") (class "Default")
      (node (ref "DD1") (pin "11") (pinfunction "P3.5/T1_11") (pintype "passive"))
    )
    (net (code "87") (name "unconnected-(DD1-P3.6{slash}~{WR}-Pad12)") (class "Default")
      (node (ref "DD1") (pin "12") (pinfunction "P3.6/~{WR}_12") (pintype "passive"))
    )
    (net (code "88") (name "unconnected-(DD1-P3.7{slash}~{RD}-Pad13)") (class "Default")
      (node (ref "DD1") (pin "13") (pinfunction "P3.7/~{RD}_13") (pintype "passive"))
    )
    (net (code "89") (name "unconnected-(DD1-RST-Pad4)") (class "Default")
      (node (ref "DD1") (pin "4") (pinfunction "RST_4") (pintype "passive"))
    )
    (net (code "90") (name "unconnected-(DD1-~{PSEN}-Pad26)") (class "Default")
      (node (ref "DD1") (pin "26") (pinfunction "~{PSEN}_26") (pintype "passive"))
    )
    (net (code "91") (name "unconnected-(U1-Pad2)") (class "Default")
      (node (ref "U1") (pin "2") (pinfunction "2_2") (pintype "passive"))
    )
    (net (code "92") (name "unconnected-(U2-Pad2)") (class "Default")
      (node (ref "U2") (pin "2") (pinfunction "2_2") (pintype "passive"))
    )
    (net (code "93") (name "unconnected-(U3-Pad2)") (class "Default")
      (node (ref "U3") (pin "2") (pinfunction "2_2") (pintype "passive"))
    )
  )
)
